# LowSpeedRegulator.net
KiCad netlist of a schematic drawn in EAGLE
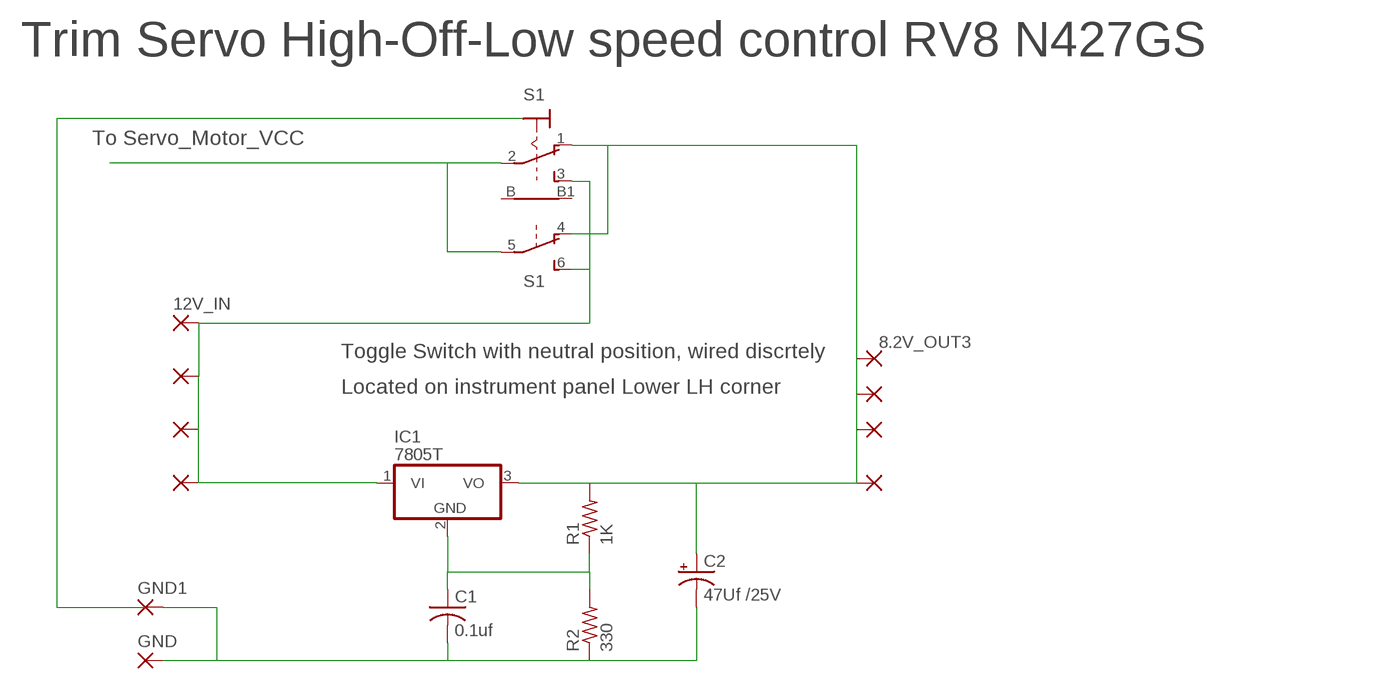
[diagram p0: schematic, sheet 1]

(export (version "E")
  (design (tool "Eeschema 10.0.6"))
  (components
    (comp (ref "6V_OUT1")
      (value "3,17/1,1")
      (footprint "eagle-import:3,17_1,1")
      (libsource (lib "eagle-import") (part "3,17/1,1"))
    )
    (comp (ref "6V_OUT2")
      (value "3,17/1,1")
      (footprint "eagle-import:3,17_1,1")
      (libsource (lib "eagle-import") (part "3,17/1,1"))
    )
    (comp (ref "6V_OUT4")
      (value "3,17/1,1")
      (footprint "eagle-import:3,17_1,1")
      (libsource (lib "eagle-import") (part "3,17/1,1"))
    )
    (comp (ref "8.2V_OUT3")
      (value "3,17/1,1")
      (footprint "eagle-import:3,17_1,1")
      (libsource (lib "eagle-import") (part "3,17/1,1"))
    )
    (comp (ref "12V")
      (value "3,17/1,1")
      (footprint "eagle-import:3,17_1,1")
      (libsource (lib "eagle-import") (part "3,17/1,1"))
    )
    (comp (ref "12V_IN")
      (value "3,17/1,1")
      (footprint "eagle-import:3,17_1,1")
      (libsource (lib "eagle-import") (part "3,17/1,1"))
    )
    (comp (ref "12_V")
      (value "3,17/1,1")
      (footprint "eagle-import:3,17_1,1")
      (libsource (lib "eagle-import") (part "3,17/1,1"))
    )
    (comp (ref "12_V2")
      (value "3,17/1,1")
      (footprint "eagle-import:3,17_1,1")
      (libsource (lib "eagle-import") (part "3,17/1,1"))
    )
    (comp (ref "C1")
      (value "0.1uf")
      (footprint "eagle-import:C0805K")
      (libsource (lib "eagle-import") (part "C-USC0805K"))
    )
    (comp (ref "C2")
      (value "47Uf /25V")
      (footprint "eagle-import:SMC_D")
      (libsource (lib "eagle-import") (part "CPOL-USSMCD"))
    )
    (comp (ref "GND")
      (value "3,17/1,1")
      (footprint "eagle-import:3,17_1,1")
      (libsource (lib "eagle-import") (part "3,17/1,1"))
    )
    (comp (ref "GND1")
      (value "3,17/1,1")
      (footprint "eagle-import:3,17_1,1")
      (libsource (lib "eagle-import") (part "3,17/1,1"))
    )
    (comp (ref "IC1")
      (value "7805T")
      (footprint "eagle-import:TO220H")
      (libsource (lib "eagle-import") (part "78T05"))
    )
    (comp (ref "R1")
      (value "1K")
      (footprint "eagle-import:R0805W")
      (libsource (lib "eagle-import") (part "R-US_R0805W"))
    )
    (comp (ref "R2")
      (value "330")
      (footprint "eagle-import:R0805W")
      (libsource (lib "eagle-import") (part "R-US_R0805W"))
    )
    (comp (ref "S1")
      (value "316-923")
      (footprint "eagle-import:316-923")
      (libsource (lib "eagle-import") (part "316-923"))
    )
  )
  (nets
    (net (code "1") (name "Net-(6V_OUT1-P)") (class "Default")
      (node (ref "6V_OUT1") (pin "1") (pinfunction "P_1") (pintype "passive"))
      (node (ref "6V_OUT2") (pin "1") (pinfunction "P_1") (pintype "passive"))
      (node (ref "6V_OUT4") (pin "1") (pinfunction "P_1") (pintype "passive"))
      (node (ref "8.2V_OUT3") (pin "1") (pinfunction "P_1") (pintype "passive"))
      (node (ref "C2") (pin "+") (pinfunction "+_+") (pintype "passive"))
      (node (ref "IC1") (pin "3") (pinfunction "VO_3") (pintype "passive"))
      (node (ref "R1") (pin "2") (pinfunction "2_2") (pintype "passive"))
      (node (ref "S1") (pin "1") (pinfunction "O_1") (pintype "passive"))
      (node (ref "S1") (pin "4") (pinfunction "O_4") (pintype "passive"))
    )
    (net (code "2") (name "Net-(12V-P)") (class "Default")
      (node (ref "12V") (pin "1") (pinfunction "P_1") (pintype "passive"))
      (node (ref "12V_IN") (pin "1") (pinfunction "P_1") (pintype "passive"))
      (node (ref "12_V") (pin "1") (pinfunction "P_1") (pintype "passive"))
      (node (ref "12_V2") (pin "1") (pinfunction "P_1") (pintype "passive"))
      (node (ref "IC1") (pin "1") (pinfunction "VI_1") (pintype "input"))
      (node (ref "S1") (pin "3") (pinfunction "S_3") (pintype "passive"))
      (node (ref "S1") (pin "6") (pinfunction "S_6") (pintype "passive"))
    )
    (net (code "3") (name "Net-(GND-P)") (class "Default")
      (node (ref "C1") (pin "2") (pinfunction "2_2") (pintype "passive"))
      (node (ref "C2") (pin "-") (pinfunction "-_-") (pintype "passive"))
      (node (ref "GND") (pin "1") (pinfunction "P_1") (pintype "passive"))
      (node (ref "GND1") (pin "1") (pinfunction "P_1") (pintype "passive"))
      (node (ref "R2") (pin "1") (pinfunction "1_1") (pintype "passive"))
    )
    (net (code "4") (name "Net-(IC1-GND)") (class "Default")
      (node (ref "C1") (pin "1") (pinfunction "1_1") (pintype "passive"))
      (node (ref "IC1") (pin "2") (pinfunction "GND_2") (pintype "passive"))
      (node (ref "R1") (pin "1") (pinfunction "1_1") (pintype "passive"))
      (node (ref "R2") (pin "2") (pinfunction "2_2") (pintype "passive"))
    )
    (net (code "5") (name "Net-(S1A-P)") (class "Default")
      (node (ref "S1") (pin "2") (pinfunction "P_2") (pintype "passive"))
      (node (ref "S1") (pin "5") (pinfunction "P_5") (pintype "passive"))
    )
    (net (code "6") (name "unconnected-(S1-PadB)") (class "Default")
      (node (ref "S1") (pin "B") (pinfunction "B_B") (pintype "passive"))
    )
    (net (code "7") (name "unconnected-(S1-PadB1)") (class "Default")
      (node (ref "S1") (pin "B1") (pinfunction "B1_B1") (pintype "passive"))
    )
  )
)
